# DetBackplaneSingleLayer01.net
KiCad netlist of a schematic drawn in EAGLE
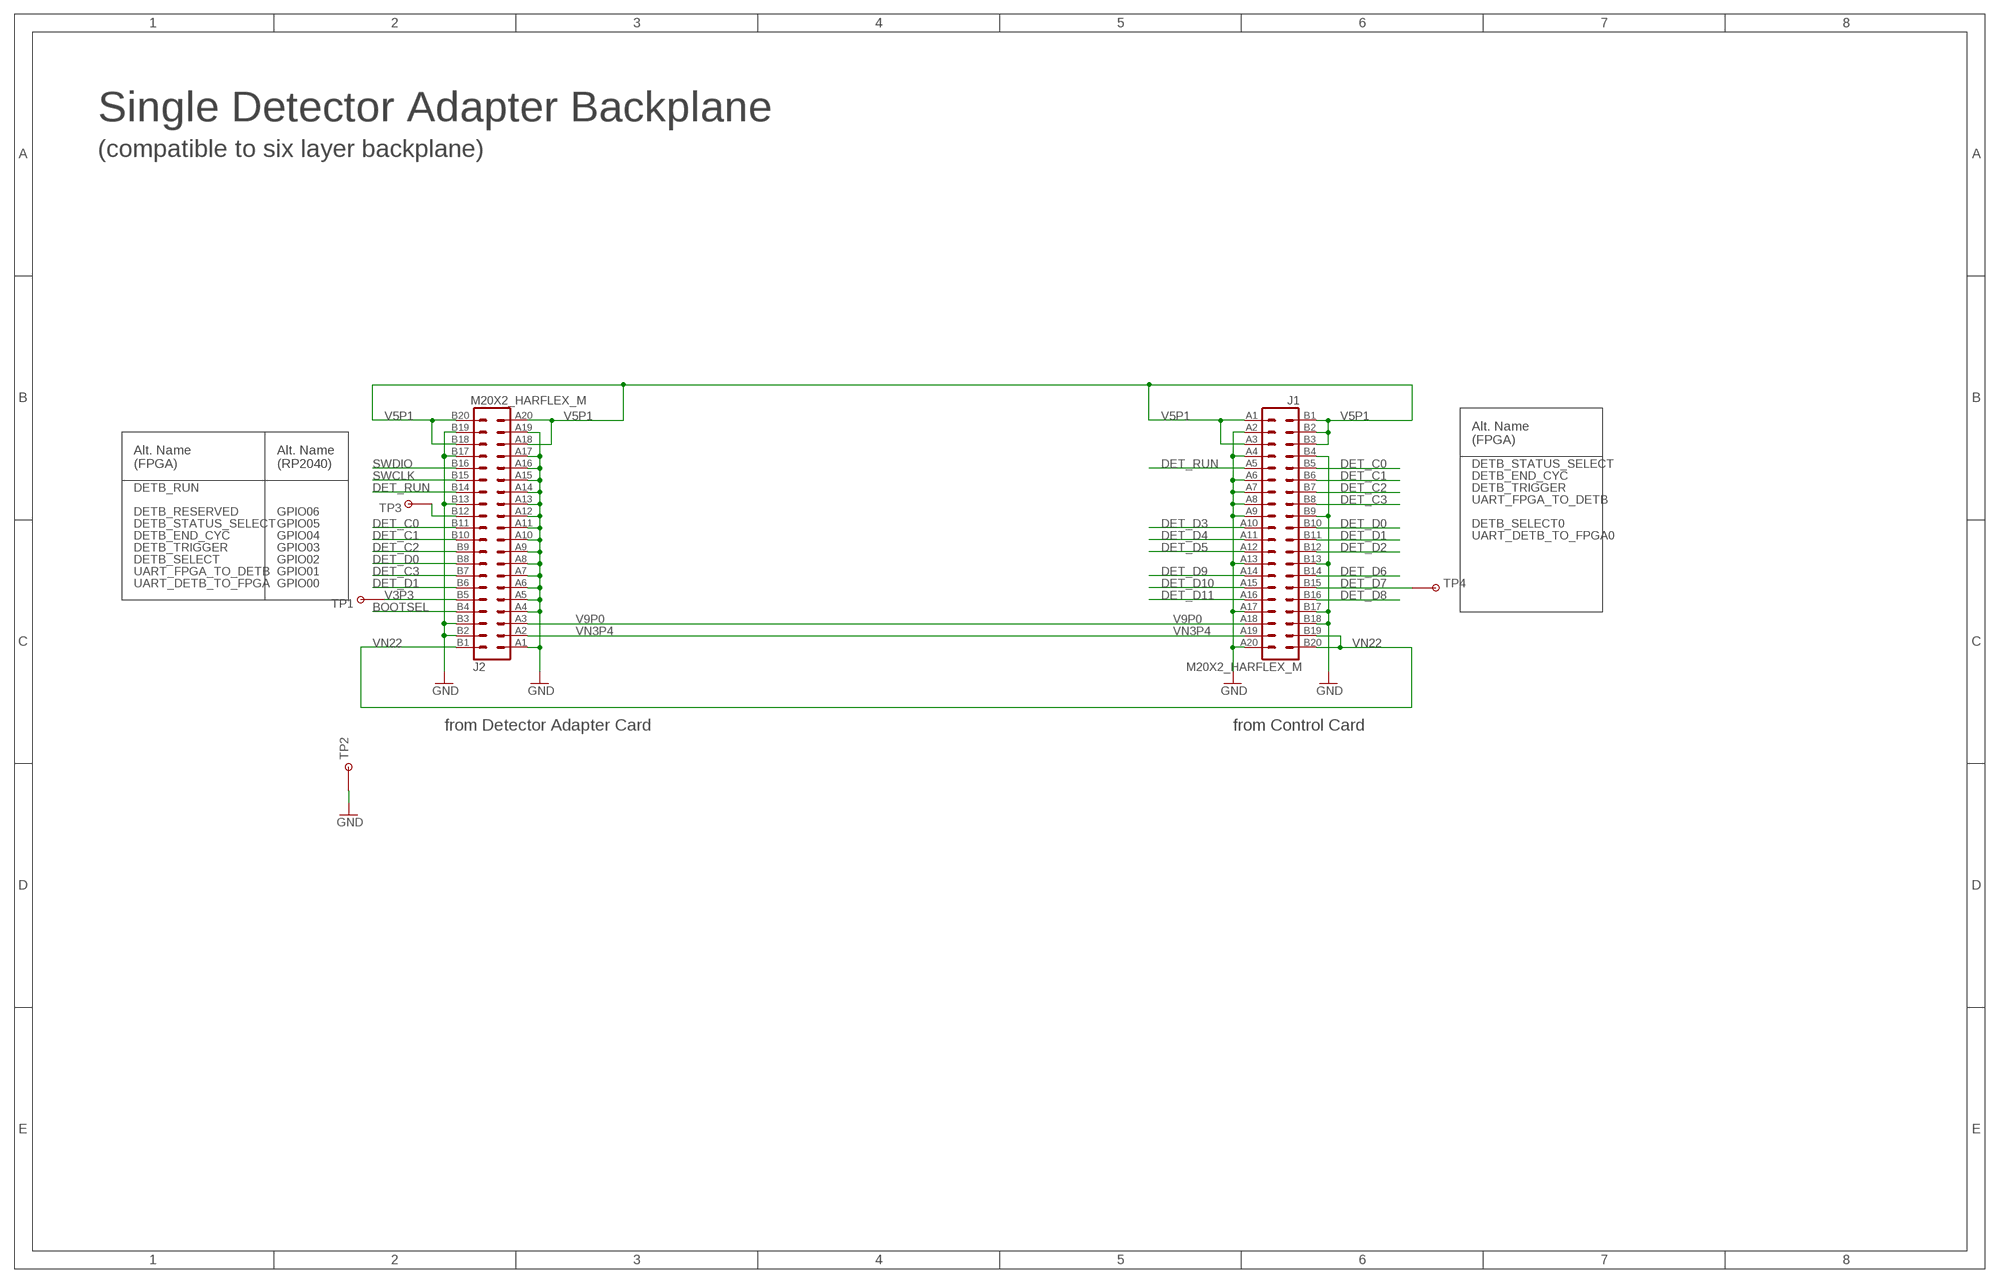
[diagram p0: schematic, sheet 1]

(export (version "E")
  (design (tool "Eeschema 10.0.6"))
  (components
    (comp (ref "J1")
      (value "M20X2_HARFLEX_M")
      (footprint "eagle-import:M20X2_HARFLEX_M")
      (libsource (lib "eagle-import") (part "M20X2_HARFLEX_M"))
    )
    (comp (ref "J2")
      (value "M20X2_HARFLEX_M")
      (footprint "eagle-import:M20X2_HARFLEX_M")
      (libsource (lib "eagle-import") (part "M20X2_HARFLEX_M"))
    )
    (comp (ref "TP1")
      (value "TESTPOINT_ROUND")
      (footprint "eagle-import:TESTPAD_ROUND")
      (libsource (lib "eagle-import") (part "TESTPOINT_ROUND"))
    )
    (comp (ref "TP2")
      (value "TESTPOINT1X01")
      (footprint "eagle-import:1X01")
      (libsource (lib "eagle-import") (part "TESTPOINT1X01"))
    )
    (comp (ref "TP3")
      (value "TESTPOINT_ROUND")
      (footprint "eagle-import:TESTPAD_ROUND")
      (libsource (lib "eagle-import") (part "TESTPOINT_ROUND"))
    )
    (comp (ref "TP4")
      (value "TESTPOINT_ROUND")
      (footprint "eagle-import:TESTPAD_ROUND")
      (libsource (lib "eagle-import") (part "TESTPOINT_ROUND"))
    )
  )
  (nets
    (net (code "1") (name "/BOOTSEL") (class "Default")
      (node (ref "J2") (pin "B4") (pinfunction "7_B4") (pintype "passive"))
    )
    (net (code "2") (name "/DET_C0") (class "Default")
      (node (ref "J1") (pin "B5") (pinfunction "9_B5") (pintype "passive"))
      (node (ref "J2") (pin "B11") (pinfunction "21_B11") (pintype "passive"))
    )
    (net (code "3") (name "/DET_C1") (class "Default")
      (node (ref "J1") (pin "B6") (pinfunction "11_B6") (pintype "passive"))
      (node (ref "J2") (pin "B10") (pinfunction "19_B10") (pintype "passive"))
    )
    (net (code "4") (name "/DET_C2") (class "Default")
      (node (ref "J1") (pin "B7") (pinfunction "13_B7") (pintype "passive"))
      (node (ref "J2") (pin "B9") (pinfunction "17_B9") (pintype "passive"))
    )
    (net (code "5") (name "/DET_C3") (class "Default")
      (node (ref "J1") (pin "B8") (pinfunction "15_B8") (pintype "passive"))
      (node (ref "J2") (pin "B7") (pinfunction "13_B7") (pintype "passive"))
    )
    (net (code "6") (name "/DET_D0") (class "Default")
      (node (ref "J1") (pin "B10") (pinfunction "19_B10") (pintype "passive"))
      (node (ref "J2") (pin "B8") (pinfunction "15_B8") (pintype "passive"))
    )
    (net (code "7") (name "/DET_D1") (class "Default")
      (node (ref "J1") (pin "B11") (pinfunction "21_B11") (pintype "passive"))
      (node (ref "J2") (pin "B6") (pinfunction "11_B6") (pintype "passive"))
    )
    (net (code "8") (name "/DET_D2") (class "Default")
      (node (ref "J1") (pin "B12") (pinfunction "23_B12") (pintype "passive"))
    )
    (net (code "9") (name "/DET_D3") (class "Default")
      (node (ref "J1") (pin "A10") (pinfunction "20_A10") (pintype "passive"))
    )
    (net (code "10") (name "/DET_D4") (class "Default")
      (node (ref "J1") (pin "A11") (pinfunction "22_A11") (pintype "passive"))
    )
    (net (code "11") (name "/DET_D5") (class "Default")
      (node (ref "J1") (pin "A12") (pinfunction "24_A12") (pintype "passive"))
    )
    (net (code "12") (name "/DET_D6") (class "Default")
      (node (ref "J1") (pin "B14") (pinfunction "27_B14") (pintype "passive"))
    )
    (net (code "13") (name "/DET_D7") (class "Default")
      (node (ref "J1") (pin "B15") (pinfunction "29_B15") (pintype "passive"))
      (node (ref "TP4") (pin "P$1") (pinfunction "P$1_P$1") (pintype "bidirectional"))
    )
    (net (code "14") (name "/DET_D8") (class "Default")
      (node (ref "J1") (pin "B16") (pinfunction "31_B16") (pintype "passive"))
    )
    (net (code "15") (name "/DET_D9") (class "Default")
      (node (ref "J1") (pin "A14") (pinfunction "28_A14") (pintype "passive"))
    )
    (net (code "16") (name "/DET_D10") (class "Default")
      (node (ref "J1") (pin "A15") (pinfunction "30_A15") (pintype "passive"))
    )
    (net (code "17") (name "/DET_D11") (class "Default")
      (node (ref "J1") (pin "A16") (pinfunction "32_A16") (pintype "passive"))
    )
    (net (code "18") (name "/DET_RUN") (class "Default")
      (node (ref "J1") (pin "A5") (pinfunction "10_A5") (pintype "passive"))
      (node (ref "J2") (pin "B14") (pinfunction "27_B14") (pintype "passive"))
    )
    (net (code "19") (name "/SWCLK") (class "Default")
      (node (ref "J2") (pin "B15") (pinfunction "29_B15") (pintype "passive"))
    )
    (net (code "20") (name "/SWDIO") (class "Default")
      (node (ref "J2") (pin "B16") (pinfunction "31_B16") (pintype "passive"))
    )
    (net (code "21") (name "/V3P3") (class "Default")
      (node (ref "J2") (pin "B5") (pinfunction "9_B5") (pintype "passive"))
      (node (ref "TP1") (pin "P$1") (pinfunction "P$1_P$1") (pintype "bidirectional"))
    )
    (net (code "22") (name "/V5P1") (class "Default")
      (node (ref "J1") (pin "A1") (pinfunction "2_A1") (pintype "passive"))
      (node (ref "J1") (pin "A3") (pinfunction "6_A3") (pintype "passive"))
      (node (ref "J1") (pin "B1") (pinfunction "1_B1") (pintype "passive"))
      (node (ref "J1") (pin "B2") (pinfunction "3_B2") (pintype "passive"))
      (node (ref "J1") (pin "B3") (pinfunction "5_B3") (pintype "passive"))
      (node (ref "J2") (pin "A18") (pinfunction "36_A18") (pintype "passive"))
      (node (ref "J2") (pin "A20") (pinfunction "40_A20") (pintype "passive"))
      (node (ref "J2") (pin "B18") (pinfunction "35_B18") (pintype "passive"))
      (node (ref "J2") (pin "B20") (pinfunction "39_B20") (pintype "passive"))
    )
    (net (code "23") (name "/V9P0") (class "Default")
      (node (ref "J1") (pin "A18") (pinfunction "36_A18") (pintype "passive"))
      (node (ref "J2") (pin "A3") (pinfunction "6_A3") (pintype "passive"))
    )
    (net (code "24") (name "/VN3P4") (class "Default")
      (node (ref "J1") (pin "A19") (pinfunction "38_A19") (pintype "passive"))
      (node (ref "J2") (pin "A2") (pinfunction "4_A2") (pintype "passive"))
    )
    (net (code "25") (name "/VN22") (class "Default")
      (node (ref "J1") (pin "B19") (pinfunction "37_B19") (pintype "passive"))
      (node (ref "J1") (pin "B20") (pinfunction "39_B20") (pintype "passive"))
      (node (ref "J2") (pin "B1") (pinfunction "1_B1") (pintype "passive"))
    )
    (net (code "26") (name "GND") (class "Default")
      (node (ref "J1") (pin "A13") (pinfunction "26_A13") (pintype "passive"))
      (node (ref "J1") (pin "A17") (pinfunction "34_A17") (pintype "passive"))
      (node (ref "J1") (pin "A2") (pinfunction "4_A2") (pintype "passive"))
      (node (ref "J1") (pin "A20") (pinfunction "40_A20") (pintype "passive"))
      (node (ref "J1") (pin "A4") (pinfunction "8_A4") (pintype "passive"))
      (node (ref "J1") (pin "A6") (pinfunction "12_A6") (pintype "passive"))
      (node (ref "J1") (pin "A7") (pinfunction "14_A7") (pintype "passive"))
      (node (ref "J1") (pin "A8") (pinfunction "16_A8") (pintype "passive"))
      (node (ref "J1") (pin "A9") (pinfunction "18_A9") (pintype "passive"))
      (node (ref "J1") (pin "B13") (pinfunction "25_B13") (pintype "passive"))
      (node (ref "J1") (pin "B17") (pinfunction "33_B17") (pintype "passive"))
      (node (ref "J1") (pin "B18") (pinfunction "35_B18") (pintype "passive"))
      (node (ref "J1") (pin "B4") (pinfunction "7_B4") (pintype "passive"))
      (node (ref "J1") (pin "B9") (pinfunction "17_B9") (pintype "passive"))
      (node (ref "J2") (pin "A1") (pinfunction "2_A1") (pintype "passive"))
      (node (ref "J2") (pin "A10") (pinfunction "20_A10") (pintype "passive"))
      (node (ref "J2") (pin "A11") (pinfunction "22_A11") (pintype "passive"))
      (node (ref "J2") (pin "A12") (pinfunction "24_A12") (pintype "passive"))
      (node (ref "J2") (pin "A13") (pinfunction "26_A13") (pintype "passive"))
      (node (ref "J2") (pin "A14") (pinfunction "28_A14") (pintype "passive"))
      (node (ref "J2") (pin "A15") (pinfunction "30_A15") (pintype "passive"))
      (node (ref "J2") (pin "A16") (pinfunction "32_A16") (pintype "passive"))
      (node (ref "J2") (pin "A17") (pinfunction "34_A17") (pintype "passive"))
      (node (ref "J2") (pin "A19") (pinfunction "38_A19") (pintype "passive"))
      (node (ref "J2") (pin "A4") (pinfunction "8_A4") (pintype "passive"))
      (node (ref "J2") (pin "A5") (pinfunction "10_A5") (pintype "passive"))
      (node (ref "J2") (pin "A6") (pinfunction "12_A6") (pintype "passive"))
      (node (ref "J2") (pin "A7") (pinfunction "14_A7") (pintype "passive"))
      (node (ref "J2") (pin "A8") (pinfunction "16_A8") (pintype "passive"))
      (node (ref "J2") (pin "A9") (pinfunction "18_A9") (pintype "passive"))
      (node (ref "J2") (pin "B13") (pinfunction "25_B13") (pintype "passive"))
      (node (ref "J2") (pin "B17") (pinfunction "33_B17") (pintype "passive"))
      (node (ref "J2") (pin "B19") (pinfunction "37_B19") (pintype "passive"))
      (node (ref "J2") (pin "B2") (pinfunction "3_B2") (pintype "passive"))
      (node (ref "J2") (pin "B3") (pinfunction "5_B3") (pintype "passive"))
      (node (ref "TP2") (pin "1") (pinfunction "P$1_1") (pintype "bidirectional"))
    )
    (net (code "27") (name "Net-(J2-23)") (class "Default")
      (node (ref "J2") (pin "B12") (pinfunction "23_B12") (pintype "passive"))
      (node (ref "TP3") (pin "P$1") (pinfunction "P$1_P$1") (pintype "bidirectional"))
    )
  )
)
